# CircuitoMedidorADE.net
KiCad netlist of a schematic drawn in Altium Designer
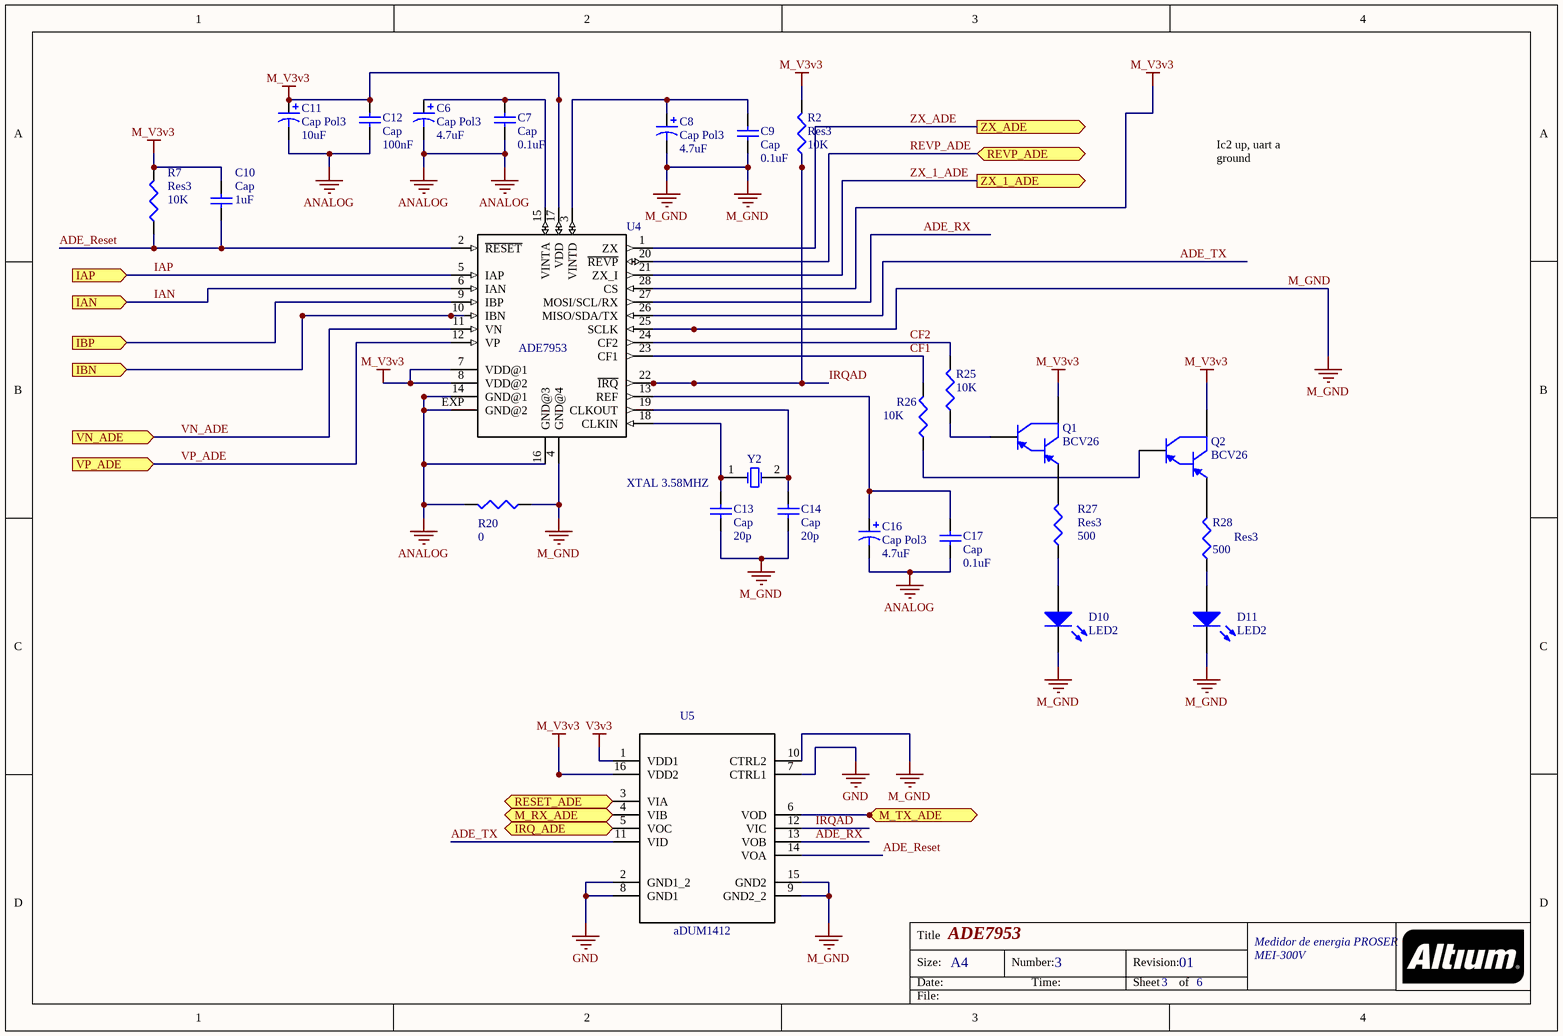
[diagram p0: CircuitoMedidorADE.SchDoc]

(export (version "E")
  (design (tool "Eeschema 10.0.6"))
  (components
    (comp (ref "C6")
      (value "Cap Pol3")
      (footprint "Custom0805")
      (description "Polarized Capacitor (Surface Mount)")
      (fields (field (name "ALTIUM_VALUE") "4.7uF") (field (name "PUBLISHER") "Altium Limited"))
      (libsource (lib "Miscellaneous Devices") (part "Cap Pol3"))
    )
    (comp (ref "C7")
      (value "Cap")
      (footprint "Custom0805")
      (description "Capacitor")
      (fields (field (name "ALTIUM_VALUE") "0.1uF") (field (name "PUBLISHER") "Altium Limited"))
      (libsource (lib "Miscellaneous Devices") (part "Cap"))
    )
    (comp (ref "C8")
      (value "Cap Pol3")
      (footprint "Custom0805")
      (description "Polarized Capacitor (Surface Mount)")
      (fields (field (name "ALTIUM_VALUE") "4.7uF") (field (name "PUBLISHER") "Altium Limited"))
      (libsource (lib "Miscellaneous Devices") (part "Cap Pol3"))
    )
    (comp (ref "C9")
      (value "Cap")
      (footprint "Custom0805")
      (description "Capacitor")
      (fields (field (name "ALTIUM_VALUE") "0.1uF") (field (name "PUBLISHER") "Altium Limited"))
      (libsource (lib "Miscellaneous Devices") (part "Cap"))
    )
    (comp (ref "C10")
      (value "Cap")
      (footprint "Custom0805")
      (description "Capacitor")
      (fields (field (name "ALTIUM_VALUE") "1uF") (field (name "PUBLISHER") "Altium Limited"))
      (libsource (lib "Miscellaneous Devices") (part "Cap"))
    )
    (comp (ref "C11")
      (value "Cap Pol3")
      (footprint "Custom0805")
      (description "Polarized Capacitor (Surface Mount)")
      (fields (field (name "ALTIUM_VALUE") "10uF") (field (name "PUBLISHER") "Altium Limited"))
      (libsource (lib "Miscellaneous Devices") (part "Cap Pol3"))
    )
    (comp (ref "C12")
      (value "Cap")
      (footprint "Custom0805")
      (description "Capacitor")
      (fields (field (name "ALTIUM_VALUE") "100nF") (field (name "PUBLISHER") "Altium Limited"))
      (libsource (lib "Miscellaneous Devices") (part "Cap"))
    )
    (comp (ref "C13")
      (value "Cap")
      (footprint "Custom0805")
      (description "Capacitor")
      (fields (field (name "ALTIUM_VALUE") "20p") (field (name "PUBLISHER") "Altium Limited"))
      (libsource (lib "Miscellaneous Devices") (part "Cap"))
    )
    (comp (ref "C14")
      (value "Cap")
      (footprint "Custom0805")
      (description "Capacitor")
      (fields (field (name "ALTIUM_VALUE") "20p") (field (name "PUBLISHER") "Altium Limited"))
      (libsource (lib "Miscellaneous Devices") (part "Cap"))
    )
    (comp (ref "C16")
      (value "Cap Pol3")
      (footprint "Custom0805")
      (description "Polarized Capacitor (Surface Mount)")
      (fields (field (name "ALTIUM_VALUE") "4.7uF") (field (name "PUBLISHER") "Altium Limited"))
      (libsource (lib "Miscellaneous Devices") (part "Cap Pol3"))
    )
    (comp (ref "C17")
      (value "Cap")
      (footprint "Custom0805")
      (description "Capacitor")
      (fields (field (name "ALTIUM_VALUE") "0.1uF") (field (name "PUBLISHER") "Altium Limited"))
      (libsource (lib "Miscellaneous Devices") (part "Cap"))
    )
    (comp (ref "D10")
      (value "LED2")
      (footprint "Custom0805")
      (description "Typical RED, GREEN, YELLOW, AMBER GaAs LED")
      (fields (field (name "PUBLISHER") "Altium Limited"))
      (libsource (lib "Miscellaneous Devices") (part "LED2"))
    )
    (comp (ref "D11")
      (value "LED2")
      (footprint "Custom0805")
      (description "Typical RED, GREEN, YELLOW, AMBER GaAs LED")
      (fields (field (name "PUBLISHER") "Altium Limited"))
      (libsource (lib "Miscellaneous Devices") (part "LED2"))
    )
    (comp (ref "Q1")
      (value "BCV26")
      (footprint "SOT23_L")
      (description "PNP Darlington Bipolar Transistor")
      (fields (field (name "PUBLISHER") "Altium Limited"))
      (libsource (lib "Miscellaneous Devices") (part "PNP1"))
    )
    (comp (ref "Q2")
      (value "BCV26")
      (footprint "SOT23_L")
      (description "PNP Darlington Bipolar Transistor")
      (fields (field (name "PUBLISHER") "Altium Limited"))
      (libsource (lib "Miscellaneous Devices") (part "PNP1"))
    )
    (comp (ref "R2")
      (value "Res3")
      (footprint "Custom0805")
      (description "Resistor")
      (fields (field (name "ALTIUM_VALUE") "10K") (field (name "PUBLISHER") "Altium Limited"))
      (libsource (lib "Miscellaneous Devices") (part "Res3"))
    )
    (comp (ref "R7")
      (value "Res3")
      (footprint "Custom0805")
      (description "Resistor")
      (fields (field (name "ALTIUM_VALUE") "10K") (field (name "PUBLISHER") "Altium Limited"))
      (libsource (lib "Miscellaneous Devices") (part "Res3"))
    )
    (comp (ref "R20")
      (value "0")
      (footprint "Custom0805")
      (description "Resistor")
      (fields (field (name "Comment") "Res3") (field (name "PUBLISHER") "Altium Limited"))
      (libsource (lib "Miscellaneous Devices") (part "Res3"))
    )
    (comp (ref "R25")
      (value "10K")
      (footprint "Custom0805")
      (description "Resistor")
      (fields (field (name "Comment") "Rb") (field (name "PUBLISHER") "Altium Limited"))
      (libsource (lib "Miscellaneous Devices") (part "Res3"))
    )
    (comp (ref "R26")
      (value "10K")
      (footprint "Custom0805")
      (description "Resistor")
      (fields (field (name "Comment") "Rb") (field (name "PUBLISHER") "Altium Limited"))
      (libsource (lib "Miscellaneous Devices") (part "Res3"))
    )
    (comp (ref "R27")
      (value "Res3")
      (footprint "Custom0805")
      (description "Resistor")
      (fields (field (name "ALTIUM_VALUE") "500") (field (name "PUBLISHER") "Altium Limited"))
      (libsource (lib "Miscellaneous Devices") (part "Res3"))
    )
    (comp (ref "R28")
      (value "Res3")
      (footprint "Custom0805")
      (description "Resistor")
      (fields (field (name "ALTIUM_VALUE") "500") (field (name "PUBLISHER") "Altium Limited"))
      (libsource (lib "Miscellaneous Devices") (part "Res3"))
    )
    (comp (ref "U4")
      (value "ADE7953")
      (footprint "*LFCSP28_ADE7953(Primary)")
      (fields (field (name "MF") "Analog Devices"))
      (libsource (lib "ADE7953") (part "ADE7953"))
    )
    (comp (ref "U5")
      (value "aDUM1412")
      (footprint "*SOIC127P1032X265-16N")
      (description "Digital Isolator CMOS 4-CH 1Mbps 16-Pin SOIC W T/R")
      (fields (field (name "MP") "ADUM1411ARWZ-RL") (field (name "MF") "Analog Devices"))
      (libsource (lib "ADUM1411ARWZ-RL") (part "ADUM1411ARWZ-RL"))
    )
    (comp (ref "Y2")
      (value "XTAL 3.58MHZ")
      (footprint "XTAL1140X475X430D1315L440X63M")
      (description "Crystal Oscillator")
      (fields (field (name "PUBLISHER") "Altium Limited"))
      (libsource (lib "Miscellaneous Devices") (part "XTAL"))
    )
  )
  (nets
    (net (code "1") (name "/ADE_RX") (class "Default")
      (node (ref "U4") (pin "27") (pinfunction "MOSI/SCL/RX_27") (pintype "output"))
      (node (ref "U5") (pin "13") (pinfunction "VOB_13") (pintype "passive"))
    )
    (net (code "2") (name "/ADE_Reset") (class "Default")
      (node (ref "C10") (pin "1") (pinfunction "1_1") (pintype "passive"))
      (node (ref "R7") (pin "1") (pinfunction "1_1") (pintype "passive"))
      (node (ref "U4") (pin "2") (pinfunction "~{RESET}_2") (pintype "input"))
      (node (ref "U5") (pin "14") (pinfunction "VOA_14") (pintype "passive"))
    )
    (net (code "3") (name "/ADE_TX") (class "Default")
      (node (ref "U4") (pin "26") (pinfunction "MISO/SDA/TX_26") (pintype "input"))
      (node (ref "U5") (pin "11") (pinfunction "VID_11") (pintype "passive"))
    )
    (net (code "4") (name "/CF1") (class "Default")
      (node (ref "R26") (pin "2") (pinfunction "2_2") (pintype "passive"))
      (node (ref "U4") (pin "23") (pinfunction "CF1_23") (pintype "output"))
    )
    (net (code "5") (name "/CF2") (class "Default")
      (node (ref "R25") (pin "2") (pinfunction "2_2") (pintype "passive"))
      (node (ref "U4") (pin "24") (pinfunction "CF2_24") (pintype "output"))
    )
    (net (code "6") (name "/IAN") (class "Default")
      (node (ref "U4") (pin "6") (pinfunction "IAN_6") (pintype "input"))
    )
    (net (code "7") (name "/IAP") (class "Default")
      (node (ref "U4") (pin "5") (pinfunction "IAP_5") (pintype "input"))
    )
    (net (code "8") (name "/IBN") (class "Default")
      (node (ref "U4") (pin "10") (pinfunction "IBN_10") (pintype "input"))
    )
    (net (code "9") (name "/IBP") (class "Default")
      (node (ref "U4") (pin "9") (pinfunction "IBP_9") (pintype "input"))
    )
    (net (code "10") (name "/IRQAD") (class "Default")
      (node (ref "R2") (pin "1") (pinfunction "1_1") (pintype "passive"))
      (node (ref "U4") (pin "22") (pinfunction "~{IRQ}_22") (pintype "output"))
      (node (ref "U5") (pin "12") (pinfunction "VIC_12") (pintype "passive"))
    )
    (net (code "11") (name "/IRQ_ADE") (class "Default")
      (node (ref "U5") (pin "5") (pinfunction "VOC_5") (pintype "passive"))
    )
    (net (code "12") (name "/M_RX_ADE") (class "Default")
      (node (ref "U5") (pin "4") (pinfunction "VIB_4") (pintype "passive"))
    )
    (net (code "13") (name "/M_TX_ADE") (class "Default")
      (node (ref "U5") (pin "6") (pinfunction "VOD_6") (pintype "passive"))
    )
    (net (code "14") (name "/RESET_ADE") (class "Default")
      (node (ref "U5") (pin "3") (pinfunction "VIA_3") (pintype "passive"))
    )
    (net (code "15") (name "/REVP_ADE") (class "Default")
      (node (ref "U4") (pin "20") (pinfunction "~{REVP}_20") (pintype "bidirectional"))
    )
    (net (code "16") (name "/VN_ADE") (class "Default")
      (node (ref "U4") (pin "11") (pinfunction "VN_11") (pintype "input"))
    )
    (net (code "17") (name "/VP_ADE") (class "Default")
      (node (ref "U4") (pin "12") (pinfunction "VP_12") (pintype "input"))
    )
    (net (code "18") (name "/ZX_1_ADE") (class "Default")
      (node (ref "U4") (pin "21") (pinfunction "ZX_I_21") (pintype "output"))
    )
    (net (code "19") (name "/ZX_ADE") (class "Default")
      (node (ref "U4") (pin "1") (pinfunction "ZX_1") (pintype "output"))
    )
    (net (code "20") (name "ANALOG") (class "Default")
      (node (ref "C11") (pin "2") (pinfunction "2_2") (pintype "passive"))
      (node (ref "C12") (pin "1") (pinfunction "1_1") (pintype "passive"))
      (node (ref "C16") (pin "2") (pinfunction "2_2") (pintype "passive"))
      (node (ref "C17") (pin "1") (pinfunction "1_1") (pintype "passive"))
      (node (ref "C6") (pin "2") (pinfunction "2_2") (pintype "passive"))
      (node (ref "C7") (pin "1") (pinfunction "1_1") (pintype "passive"))
      (node (ref "R20") (pin "2") (pinfunction "2_2") (pintype "passive"))
      (node (ref "U4") (pin "14") (pinfunction "GND@1_14") (pintype "power_in"))
      (node (ref "U4") (pin "16") (pinfunction "GND@3_16") (pintype "power_in"))
      (node (ref "U4") (pin "EXP") (pinfunction "GND@2_EXP") (pintype "power_in"))
    )
    (net (code "21") (name "GND") (class "Default")
      (node (ref "U5") (pin "2") (pinfunction "GND1_2_2") (pintype "passive"))
      (node (ref "U5") (pin "7") (pinfunction "CTRL1_7") (pintype "passive"))
      (node (ref "U5") (pin "8") (pinfunction "GND1_8") (pintype "passive"))
    )
    (net (code "22") (name "M_GND") (class "Default")
      (node (ref "C13") (pin "1") (pinfunction "1_1") (pintype "passive"))
      (node (ref "C14") (pin "1") (pinfunction "1_1") (pintype "passive"))
      (node (ref "C8") (pin "2") (pinfunction "2_2") (pintype "passive"))
      (node (ref "C9") (pin "1") (pinfunction "1_1") (pintype "passive"))
      (node (ref "D10") (pin "2") (pinfunction "K_2") (pintype "passive"))
      (node (ref "D11") (pin "2") (pinfunction "K_2") (pintype "passive"))
      (node (ref "R20") (pin "1") (pinfunction "1_1") (pintype "passive"))
      (node (ref "U4") (pin "25") (pinfunction "SCLK_25") (pintype "input"))
      (node (ref "U4") (pin "4") (pinfunction "GND@4_4") (pintype "power_in"))
      (node (ref "U5") (pin "10") (pinfunction "CTRL2_10") (pintype "passive"))
      (node (ref "U5") (pin "15") (pinfunction "GND2_15") (pintype "passive"))
      (node (ref "U5") (pin "9") (pinfunction "GND2_2_9") (pintype "passive"))
    )
    (net (code "23") (name "M_V3v3") (class "Default")
      (node (ref "C10") (pin "2") (pinfunction "2_2") (pintype "passive"))
      (node (ref "C11") (pin "1") (pinfunction "1_1") (pintype "passive"))
      (node (ref "C12") (pin "2") (pinfunction "2_2") (pintype "passive"))
      (node (ref "Q1") (pin "3") (pinfunction "C_3") (pintype "passive"))
      (node (ref "Q2") (pin "3") (pinfunction "C_3") (pintype "passive"))
      (node (ref "R2") (pin "2") (pinfunction "2_2") (pintype "passive"))
      (node (ref "R7") (pin "2") (pinfunction "2_2") (pintype "passive"))
      (node (ref "U4") (pin "17") (pinfunction "VDD_17") (pintype "bidirectional"))
      (node (ref "U4") (pin "28") (pinfunction "CS_28") (pintype "input"))
      (node (ref "U4") (pin "7") (pinfunction "VDD@1_7") (pintype "power_in"))
      (node (ref "U4") (pin "8") (pinfunction "VDD@2_8") (pintype "power_in"))
      (node (ref "U5") (pin "16") (pinfunction "VDD2_16") (pintype "power_in"))
    )
    (net (code "24") (name "Net-(D10-A)") (class "Default")
      (node (ref "D10") (pin "1") (pinfunction "A_1") (pintype "passive"))
      (node (ref "R27") (pin "1") (pinfunction "1_1") (pintype "passive"))
    )
    (net (code "25") (name "Net-(D11-A)") (class "Default")
      (node (ref "D11") (pin "1") (pinfunction "A_1") (pintype "passive"))
      (node (ref "R28") (pin "1") (pinfunction "1_1") (pintype "passive"))
    )
    (net (code "26") (name "Net-(Q1-B)") (class "Default")
      (node (ref "Q1") (pin "2") (pinfunction "B_2") (pintype "passive"))
      (node (ref "R25") (pin "1") (pinfunction "1_1") (pintype "passive"))
    )
    (net (code "27") (name "Net-(Q1-E)") (class "Default")
      (node (ref "Q1") (pin "1") (pinfunction "E_1") (pintype "passive"))
      (node (ref "R27") (pin "2") (pinfunction "2_2") (pintype "passive"))
    )
    (net (code "28") (name "Net-(Q2-B)") (class "Default")
      (node (ref "Q2") (pin "2") (pinfunction "B_2") (pintype "passive"))
      (node (ref "R26") (pin "1") (pinfunction "1_1") (pintype "passive"))
    )
    (net (code "29") (name "Net-(Q2-E)") (class "Default")
      (node (ref "Q2") (pin "1") (pinfunction "E_1") (pintype "passive"))
      (node (ref "R28") (pin "2") (pinfunction "2_2") (pintype "passive"))
    )
    (net (code "30") (name "Net-(U4-CLKIN)") (class "Default")
      (node (ref "C13") (pin "2") (pinfunction "2_2") (pintype "passive"))
      (node (ref "U4") (pin "18") (pinfunction "CLKIN_18") (pintype "input"))
      (node (ref "Y2") (pin "1") (pinfunction "OSC1_1") (pintype "passive"))
    )
    (net (code "31") (name "Net-(U4-CLKOUT)") (class "Default")
      (node (ref "C14") (pin "2") (pinfunction "2_2") (pintype "passive"))
      (node (ref "U4") (pin "19") (pinfunction "CLKOUT_19") (pintype "output"))
      (node (ref "Y2") (pin "2") (pinfunction "OSC2_2") (pintype "passive"))
    )
    (net (code "32") (name "Net-(U4-REF)") (class "Default")
      (node (ref "C16") (pin "1") (pinfunction "1_1") (pintype "passive"))
      (node (ref "C17") (pin "2") (pinfunction "2_2") (pintype "passive"))
      (node (ref "U4") (pin "13") (pinfunction "REF_13") (pintype "output"))
    )
    (net (code "33") (name "Net-(U4-VINTA)") (class "Default")
      (node (ref "C6") (pin "1") (pinfunction "1_1") (pintype "passive"))
      (node (ref "C7") (pin "2") (pinfunction "2_2") (pintype "passive"))
      (node (ref "U4") (pin "15") (pinfunction "VINTA_15") (pintype "bidirectional"))
    )
    (net (code "34") (name "Net-(U4-VINTD)") (class "Default")
      (node (ref "C8") (pin "1") (pinfunction "1_1") (pintype "passive"))
      (node (ref "C9") (pin "2") (pinfunction "2_2") (pintype "passive"))
      (node (ref "U4") (pin "3") (pinfunction "VINTD_3") (pintype "bidirectional"))
    )
    (net (code "35") (name "V3v3") (class "Default")
      (node (ref "U5") (pin "1") (pinfunction "VDD1_1") (pintype "power_in"))
    )
  )
)
